# 407-485.net
KiCad netlist of a schematic drawn in Altium Designer
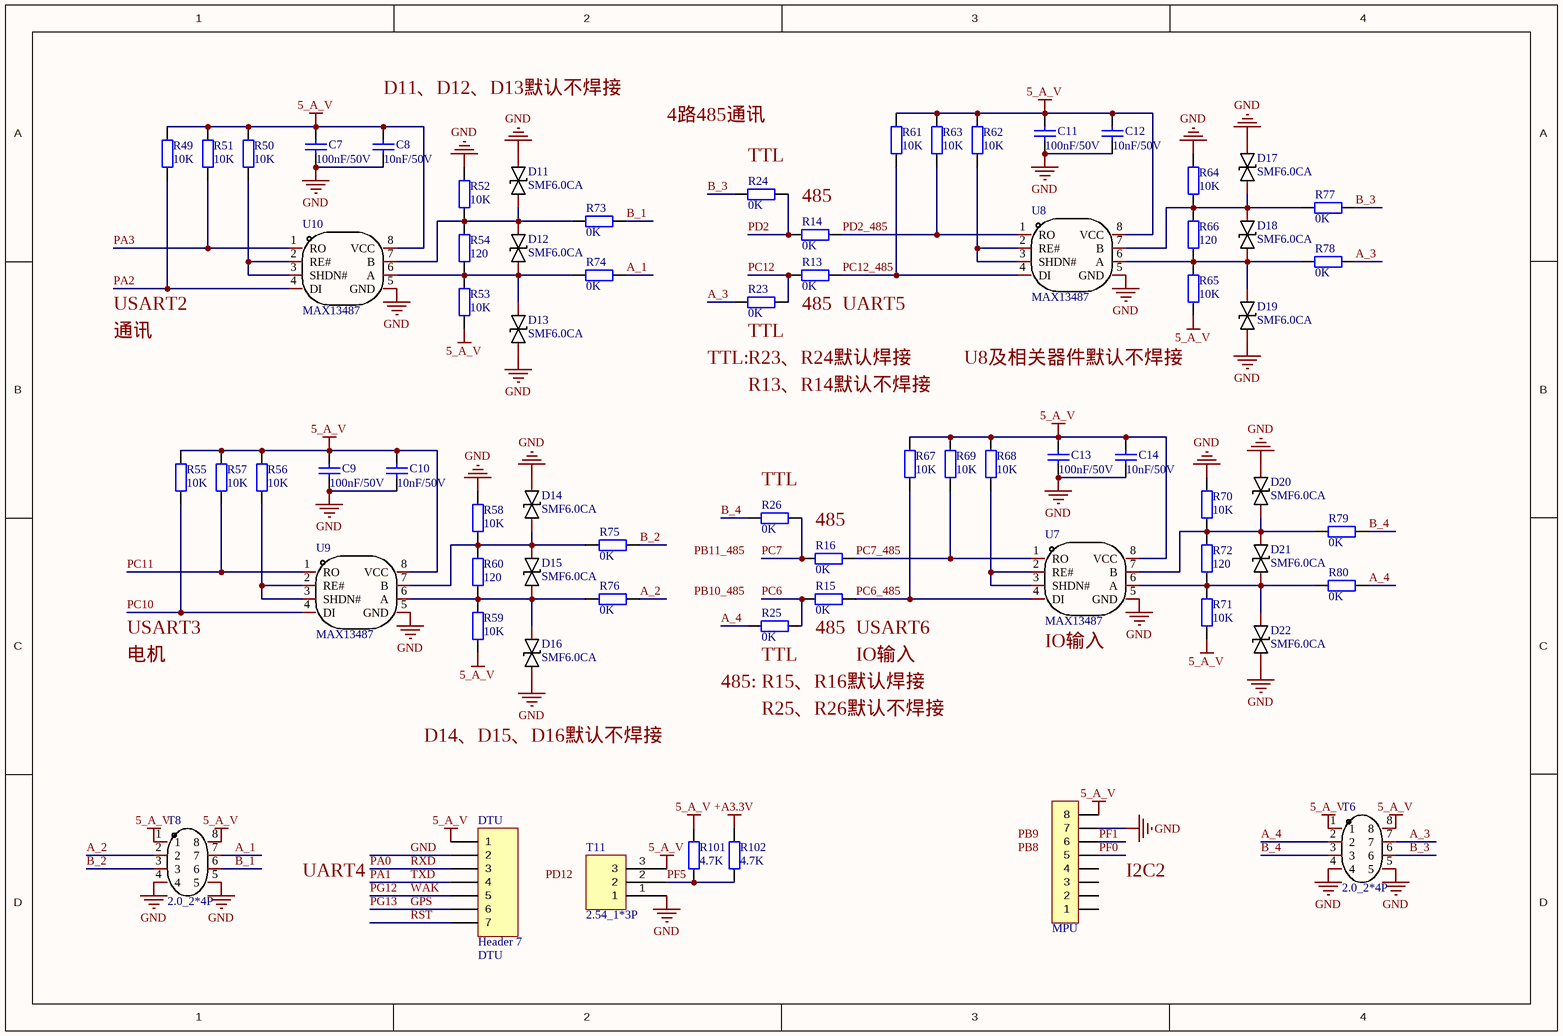
[diagram p0: 407-485.schdoc]

(export (version "E")
  (design (tool "Eeschema 10.0.6"))
  (components
    (comp (ref "C7")
      (value "100nF/50V")
      (description "Capacitor")
      (fields (field (name "PUBLISHER") "Altium Limited"))
      (libsource (lib "Miscellaneous Devices") (part "Cap"))
    )
    (comp (ref "C8")
      (value "10nF/50V")
      (description "Capacitor")
      (fields (field (name "PUBLISHER") "Altium Limited"))
      (libsource (lib "Miscellaneous Devices") (part "Cap"))
    )
    (comp (ref "C9")
      (value "100nF/50V")
      (description "Capacitor")
      (fields (field (name "PUBLISHER") "Altium Limited"))
      (libsource (lib "Miscellaneous Devices") (part "Cap"))
    )
    (comp (ref "C10")
      (value "10nF/50V")
      (description "Capacitor")
      (fields (field (name "PUBLISHER") "Altium Limited"))
      (libsource (lib "Miscellaneous Devices") (part "Cap"))
    )
    (comp (ref "C11")
      (value "100nF/50V")
      (description "Capacitor")
      (fields (field (name "PUBLISHER") "Altium Limited"))
      (libsource (lib "Miscellaneous Devices") (part "Cap"))
    )
    (comp (ref "C12")
      (value "10nF/50V")
      (description "Capacitor")
      (fields (field (name "PUBLISHER") "Altium Limited"))
      (libsource (lib "Miscellaneous Devices") (part "Cap"))
    )
    (comp (ref "C13")
      (value "100nF/50V")
      (description "Capacitor")
      (fields (field (name "PUBLISHER") "Altium Limited"))
      (libsource (lib "Miscellaneous Devices") (part "Cap"))
    )
    (comp (ref "C14")
      (value "10nF/50V")
      (description "Capacitor")
      (fields (field (name "PUBLISHER") "Altium Limited"))
      (libsource (lib "Miscellaneous Devices") (part "Cap"))
    )
    (comp (ref "D11")
      (value "SMF6.0CA")
      (footprint "SMF6.0CA")
      (libsource (lib "tianjin_2023") (part "SMF6.0CA"))
    )
    (comp (ref "D12")
      (value "SMF6.0CA")
      (footprint "SMF6.0CA")
      (libsource (lib "tianjin_2023") (part "SMF6.0CA"))
    )
    (comp (ref "D13")
      (value "SMF6.0CA")
      (footprint "SMF6.0CA")
      (libsource (lib "tianjin_2023") (part "SMF6.0CA"))
    )
    (comp (ref "D14")
      (value "SMF6.0CA")
      (footprint "SMF6.0CA")
      (libsource (lib "tianjin_2023") (part "SMF6.0CA"))
    )
    (comp (ref "D15")
      (value "SMF6.0CA")
      (footprint "SMF6.0CA")
      (libsource (lib "tianjin_2023") (part "SMF6.0CA"))
    )
    (comp (ref "D16")
      (value "SMF6.0CA")
      (footprint "SMF6.0CA")
      (libsource (lib "tianjin_2023") (part "SMF6.0CA"))
    )
    (comp (ref "D17")
      (value "SMF6.0CA")
      (footprint "SMF6.0CA")
      (libsource (lib "tianjin_2023") (part "SMF6.0CA"))
    )
    (comp (ref "D18")
      (value "SMF6.0CA")
      (footprint "SMF6.0CA")
      (libsource (lib "tianjin_2023") (part "SMF6.0CA"))
    )
    (comp (ref "D19")
      (value "SMF6.0CA")
      (footprint "SMF6.0CA")
      (libsource (lib "tianjin_2023") (part "SMF6.0CA"))
    )
    (comp (ref "D20")
      (value "SMF6.0CA")
      (footprint "SMF6.0CA")
      (libsource (lib "tianjin_2023") (part "SMF6.0CA"))
    )
    (comp (ref "D21")
      (value "SMF6.0CA")
      (footprint "SMF6.0CA")
      (libsource (lib "tianjin_2023") (part "SMF6.0CA"))
    )
    (comp (ref "D22")
      (value "SMF6.0CA")
      (footprint "SMF6.0CA")
      (libsource (lib "tianjin_2023") (part "SMF6.0CA"))
    )
    (comp (ref "DTU")
      (value "Header 7")
      (footprint "HDR1X7")
      (description "Header, 7-Pin")
      (fields (field (name "PUBLISHER") "Altium Limited"))
      (libsource (lib "Miscellaneous Connectors") (part "Header 7"))
    )
    (comp (ref "MPU")
      (value "HDR-1X8")
      (footprint "HDR2.54-M-LI-8P")
      (description "8P接插件")
      (fields (field (name "版权归属") "封装库来自淘宝 ID：黄晶宝石"))
      (libsource (lib "5.4 - 接插件-脚距2.54 (100mil) ") (part "Header 8"))
    )
    (comp (ref "R13")
      (value "0K")
      (footprint "R0603_L")
      (description "Resistor")
      (fields (field (name "PUBLISHER") "Altium Limited"))
      (libsource (lib "") (part "Res2_1"))
    )
    (comp (ref "R14")
      (value "0K")
      (footprint "R0603_L")
      (description "Resistor")
      (fields (field (name "PUBLISHER") "Altium Limited"))
      (libsource (lib "") (part "Res2_1"))
    )
    (comp (ref "R15")
      (value "0K")
      (footprint "R0603_L")
      (description "Resistor")
      (fields (field (name "PUBLISHER") "Altium Limited"))
      (libsource (lib "") (part "Res2_1"))
    )
    (comp (ref "R16")
      (value "0K")
      (footprint "R0603_L")
      (description "Resistor")
      (fields (field (name "PUBLISHER") "Altium Limited"))
      (libsource (lib "") (part "Res2_1"))
    )
    (comp (ref "R23")
      (value "0K")
      (footprint "R0603_L")
      (description "Resistor")
      (fields (field (name "PUBLISHER") "Altium Limited"))
      (libsource (lib "") (part "Res2_1"))
    )
    (comp (ref "R24")
      (value "0K")
      (footprint "R0603_L")
      (description "Resistor")
      (fields (field (name "PUBLISHER") "Altium Limited"))
      (libsource (lib "") (part "Res2_1"))
    )
    (comp (ref "R25")
      (value "0K")
      (footprint "R0603_L")
      (description "Resistor")
      (fields (field (name "PUBLISHER") "Altium Limited"))
      (libsource (lib "") (part "Res2_1"))
    )
    (comp (ref "R26")
      (value "0K")
      (footprint "R0603_L")
      (description "Resistor")
      (fields (field (name "PUBLISHER") "Altium Limited"))
      (libsource (lib "") (part "Res2_2"))
    )
    (comp (ref "R49")
      (value "10K")
      (footprint "R0603_L")
      (description "Resistor")
      (fields (field (name "PUBLISHER") "Altium Limited"))
      (libsource (lib "MOS motor driving module ") (part "Res2"))
    )
    (comp (ref "R50")
      (value "10K")
      (footprint "R0603_L")
      (description "Resistor")
      (fields (field (name "PUBLISHER") "Altium Limited"))
      (libsource (lib "MOS motor driving module ") (part "Res2"))
    )
    (comp (ref "R51")
      (value "10K")
      (footprint "R0603_L")
      (description "Resistor")
      (fields (field (name "PUBLISHER") "Altium Limited"))
      (libsource (lib "MOS motor driving module ") (part "Res2"))
    )
    (comp (ref "R52")
      (value "10K")
      (footprint "R0603_L")
      (description "Resistor")
      (fields (field (name "PUBLISHER") "Altium Limited"))
      (libsource (lib "MOS motor driving module ") (part "Res2"))
    )
    (comp (ref "R53")
      (value "10K")
      (footprint "R0603_L")
      (description "Resistor")
      (fields (field (name "PUBLISHER") "Altium Limited"))
      (libsource (lib "MOS motor driving module ") (part "Res2"))
    )
    (comp (ref "R54")
      (value "120")
      (footprint "R0603_L")
      (description "Resistor")
      (fields (field (name "PUBLISHER") "Altium Limited"))
      (libsource (lib "MOS motor driving module ") (part "Res2"))
    )
    (comp (ref "R55")
      (value "10K")
      (footprint "R0603_L")
      (description "Resistor")
      (fields (field (name "PUBLISHER") "Altium Limited"))
      (libsource (lib "MOS motor driving module ") (part "Res2"))
    )
    (comp (ref "R56")
      (value "10K")
      (footprint "R0603_L")
      (description "Resistor")
      (fields (field (name "PUBLISHER") "Altium Limited"))
      (libsource (lib "MOS motor driving module ") (part "Res2"))
    )
    (comp (ref "R57")
      (value "10K")
      (footprint "R0603_L")
      (description "Resistor")
      (fields (field (name "PUBLISHER") "Altium Limited"))
      (libsource (lib "MOS motor driving module ") (part "Res2"))
    )
    (comp (ref "R58")
      (value "10K")
      (footprint "R0603_L")
      (description "Resistor")
      (fields (field (name "PUBLISHER") "Altium Limited"))
      (libsource (lib "MOS motor driving module ") (part "Res2"))
    )
    (comp (ref "R59")
      (value "10K")
      (footprint "R0603_L")
      (description "Resistor")
      (fields (field (name "PUBLISHER") "Altium Limited"))
      (libsource (lib "MOS motor driving module ") (part "Res2"))
    )
    (comp (ref "R60")
      (value "120")
      (footprint "R0603_L")
      (description "Resistor")
      (fields (field (name "PUBLISHER") "Altium Limited"))
      (libsource (lib "MOS motor driving module ") (part "Res2"))
    )
    (comp (ref "R61")
      (value "10K")
      (footprint "R0603_L")
      (description "Resistor")
      (fields (field (name "PUBLISHER") "Altium Limited"))
      (libsource (lib "MOS motor driving module ") (part "Res2"))
    )
    (comp (ref "R62")
      (value "10K")
      (footprint "R0603_L")
      (description "Resistor")
      (fields (field (name "PUBLISHER") "Altium Limited"))
      (libsource (lib "MOS motor driving module ") (part "Res2"))
    )
    (comp (ref "R63")
      (value "10K")
      (footprint "R0603_L")
      (description "Resistor")
      (fields (field (name "PUBLISHER") "Altium Limited"))
      (libsource (lib "MOS motor driving module ") (part "Res2"))
    )
    (comp (ref "R64")
      (value "10K")
      (footprint "R0603_L")
      (description "Resistor")
      (fields (field (name "PUBLISHER") "Altium Limited"))
      (libsource (lib "MOS motor driving module ") (part "Res2"))
    )
    (comp (ref "R65")
      (value "10K")
      (footprint "R0603_L")
      (description "Resistor")
      (fields (field (name "PUBLISHER") "Altium Limited"))
      (libsource (lib "MOS motor driving module ") (part "Res2"))
    )
    (comp (ref "R66")
      (value "120")
      (footprint "R0603_L")
      (description "Resistor")
      (fields (field (name "PUBLISHER") "Altium Limited"))
      (libsource (lib "MOS motor driving module ") (part "Res2"))
    )
    (comp (ref "R67")
      (value "10K")
      (footprint "R0603_L")
      (description "Resistor")
      (fields (field (name "PUBLISHER") "Altium Limited"))
      (libsource (lib "MOS motor driving module ") (part "Res2"))
    )
    (comp (ref "R68")
      (value "10K")
      (footprint "R0603_L")
      (description "Resistor")
      (fields (field (name "PUBLISHER") "Altium Limited"))
      (libsource (lib "MOS motor driving module ") (part "Res2"))
    )
    (comp (ref "R69")
      (value "10K")
      (footprint "R0603_L")
      (description "Resistor")
      (fields (field (name "PUBLISHER") "Altium Limited"))
      (libsource (lib "MOS motor driving module ") (part "Res2"))
    )
    (comp (ref "R70")
      (value "10K")
      (footprint "R0603_L")
      (description "Resistor")
      (fields (field (name "PUBLISHER") "Altium Limited"))
      (libsource (lib "MOS motor driving module ") (part "Res2"))
    )
    (comp (ref "R71")
      (value "10K")
      (footprint "R0603_L")
      (description "Resistor")
      (fields (field (name "PUBLISHER") "Altium Limited"))
      (libsource (lib "MOS motor driving module ") (part "Res2"))
    )
    (comp (ref "R72")
      (value "120")
      (footprint "R0603_L")
      (description "Resistor")
      (fields (field (name "PUBLISHER") "Altium Limited"))
      (libsource (lib "MOS motor driving module ") (part "Res2"))
    )
    (comp (ref "R73")
      (value "0K")
      (footprint "R0603_L")
      (description "Resistor")
      (fields (field (name "PUBLISHER") "Altium Limited"))
      (libsource (lib "") (part "Res2_1"))
    )
    (comp (ref "R74")
      (value "0K")
      (footprint "R0603_L")
      (description "Resistor")
      (fields (field (name "PUBLISHER") "Altium Limited"))
      (libsource (lib "") (part "Res2_1"))
    )
    (comp (ref "R75")
      (value "0K")
      (footprint "R0603_L")
      (description "Resistor")
      (fields (field (name "PUBLISHER") "Altium Limited"))
      (libsource (lib "") (part "Res2_1"))
    )
    (comp (ref "R76")
      (value "0K")
      (footprint "R0603_L")
      (description "Resistor")
      (fields (field (name "PUBLISHER") "Altium Limited"))
      (libsource (lib "") (part "Res2_1"))
    )
    (comp (ref "R77")
      (value "0K")
      (footprint "R0603_L")
      (description "Resistor")
      (fields (field (name "PUBLISHER") "Altium Limited"))
      (libsource (lib "") (part "Res2_1"))
    )
    (comp (ref "R78")
      (value "0K")
      (footprint "R0603_L")
      (description "Resistor")
      (fields (field (name "PUBLISHER") "Altium Limited"))
      (libsource (lib "") (part "Res2_1"))
    )
    (comp (ref "R79")
      (value "0K")
      (footprint "R0603_L")
      (description "Resistor")
      (fields (field (name "PUBLISHER") "Altium Limited"))
      (libsource (lib "") (part "Res2_1"))
    )
    (comp (ref "R80")
      (value "0K")
      (footprint "R0603_L")
      (description "Resistor")
      (fields (field (name "PUBLISHER") "Altium Limited"))
      (libsource (lib "") (part "Res2_1"))
    )
    (comp (ref "R101")
      (value "4.7K")
      (description "Resistor")
      (fields (field (name "PUBLISHER") "Altium Limited"))
      (libsource (lib "MOS motor driving module ") (part "Res2"))
    )
    (comp (ref "R102")
      (value "4.7K")
      (description "Resistor")
      (fields (field (name "PUBLISHER") "Altium Limited"))
      (libsource (lib "MOS motor driving module ") (part "Res2"))
    )
    (comp (ref "T6")
      (value "2.0_2*4P")
      (footprint "2.0_2*4P")
      (libsource (lib "tianjin_2023") (part "2.0_2*4P"))
    )
    (comp (ref "T8")
      (value "2.0_2*4P")
      (footprint "2.0_2*4P")
      (libsource (lib "tianjin_2023") (part "2.0_2*4P"))
    )
    (comp (ref "T11")
      (value "2.54_1*3P")
      (footprint "2.54_1*3P")
      (libsource (lib "tianjin_2023") (part "2.54_1*3P"))
    )
    (comp (ref "U7")
      (value "MAX13487")
      (footprint "MAX13487")
      (libsource (lib "tianjin_2023") (part "MAX13487"))
    )
    (comp (ref "U8")
      (value "MAX13487")
      (footprint "MAX13487")
      (libsource (lib "tianjin_2023") (part "MAX13487"))
    )
    (comp (ref "U9")
      (value "MAX13487")
      (footprint "MAX13487")
      (libsource (lib "tianjin_2023") (part "MAX13487"))
    )
    (comp (ref "U10")
      (value "MAX13487")
      (footprint "MAX13487")
      (libsource (lib "tianjin_2023") (part "MAX13487"))
    )
  )
  (nets
    (net (code "1") (name "+A3.3V") (class "Default")
      (node (ref "R102") (pin "2") (pinfunction "2_2") (pintype "passive"))
    )
    (net (code "2") (name "/A_1") (class "Default")
      (node (ref "R74") (pin "1") (pinfunction "1_1") (pintype "passive"))
      (node (ref "T8") (pin "7") (pinfunction "7_7") (pintype "passive"))
    )
    (net (code "3") (name "/A_2") (class "Default")
      (node (ref "R76") (pin "1") (pinfunction "1_1") (pintype "passive"))
      (node (ref "T8") (pin "2") (pinfunction "2_2") (pintype "passive"))
    )
    (net (code "4") (name "/A_3") (class "Default")
      (node (ref "R23") (pin "2") (pinfunction "2_2") (pintype "passive"))
      (node (ref "R78") (pin "1") (pinfunction "1_1") (pintype "passive"))
      (node (ref "T6") (pin "7") (pinfunction "7_7") (pintype "passive"))
    )
    (net (code "5") (name "/A_4") (class "Default")
      (node (ref "R25") (pin "2") (pinfunction "2_2") (pintype "passive"))
      (node (ref "R80") (pin "1") (pinfunction "1_1") (pintype "passive"))
      (node (ref "T6") (pin "2") (pinfunction "2_2") (pintype "passive"))
    )
    (net (code "6") (name "/B_1") (class "Default")
      (node (ref "R73") (pin "1") (pinfunction "1_1") (pintype "passive"))
      (node (ref "T8") (pin "6") (pinfunction "6_6") (pintype "passive"))
    )
    (net (code "7") (name "/B_2") (class "Default")
      (node (ref "R75") (pin "1") (pinfunction "1_1") (pintype "passive"))
      (node (ref "T8") (pin "3") (pinfunction "3_3") (pintype "passive"))
    )
    (net (code "8") (name "/B_3") (class "Default")
      (node (ref "R24") (pin "2") (pinfunction "2_2") (pintype "passive"))
      (node (ref "R77") (pin "1") (pinfunction "1_1") (pintype "passive"))
      (node (ref "T6") (pin "6") (pinfunction "6_6") (pintype "passive"))
    )
    (net (code "9") (name "/B_4") (class "Default")
      (node (ref "R26") (pin "1") (pinfunction "1_1") (pintype "passive"))
      (node (ref "R79") (pin "1") (pinfunction "1_1") (pintype "passive"))
      (node (ref "T6") (pin "3") (pinfunction "3_3") (pintype "passive"))
    )
    (net (code "10") (name "/GPS") (class "Default")
      (node (ref "DTU") (pin "6") (pinfunction "6_6") (pintype "passive"))
    )
    (net (code "11") (name "/PA0") (class "Default")
      (node (ref "DTU") (pin "3") (pinfunction "3_3") (pintype "passive"))
    )
    (net (code "12") (name "/PA1") (class "Default")
      (node (ref "DTU") (pin "4") (pinfunction "4_4") (pintype "passive"))
    )
    (net (code "13") (name "/PA2") (class "Default")
      (node (ref "R49") (pin "1") (pinfunction "1_1") (pintype "passive"))
      (node (ref "U10") (pin "4") (pinfunction "DI_4") (pintype "passive"))
    )
    (net (code "14") (name "/PA3") (class "Default")
      (node (ref "R51") (pin "1") (pinfunction "1_1") (pintype "passive"))
      (node (ref "U10") (pin "1") (pinfunction "RO_1") (pintype "passive"))
    )
    (net (code "19") (name "/PC6") (class "Default")
      (node (ref "R15") (pin "2") (pinfunction "2_2") (pintype "passive"))
      (node (ref "R25") (pin "1") (pinfunction "1_1") (pintype "passive"))
    )
    (net (code "20") (name "/PC6_485") (class "Default")
      (node (ref "R15") (pin "1") (pinfunction "1_1") (pintype "passive"))
      (node (ref "R67") (pin "1") (pinfunction "1_1") (pintype "passive"))
      (node (ref "U7") (pin "4") (pinfunction "DI_4") (pintype "passive"))
    )
    (net (code "21") (name "/PC7") (class "Default")
      (node (ref "R16") (pin "2") (pinfunction "2_2") (pintype "passive"))
      (node (ref "R26") (pin "2") (pinfunction "2_2") (pintype "passive"))
    )
    (net (code "22") (name "/PC7_485") (class "Default")
      (node (ref "R16") (pin "1") (pinfunction "1_1") (pintype "passive"))
      (node (ref "R69") (pin "1") (pinfunction "1_1") (pintype "passive"))
      (node (ref "U7") (pin "1") (pinfunction "RO_1") (pintype "passive"))
    )
    (net (code "23") (name "/PC10") (class "Default")
      (node (ref "R55") (pin "1") (pinfunction "1_1") (pintype "passive"))
      (node (ref "U9") (pin "4") (pinfunction "DI_4") (pintype "passive"))
    )
    (net (code "24") (name "/PC11") (class "Default")
      (node (ref "R57") (pin "1") (pinfunction "1_1") (pintype "passive"))
      (node (ref "U9") (pin "1") (pinfunction "RO_1") (pintype "passive"))
    )
    (net (code "25") (name "/PC12") (class "Default")
      (node (ref "R13") (pin "2") (pinfunction "2_2") (pintype "passive"))
      (node (ref "R23") (pin "1") (pinfunction "1_1") (pintype "passive"))
    )
    (net (code "26") (name "/PC12_485") (class "Default")
      (node (ref "R13") (pin "1") (pinfunction "1_1") (pintype "passive"))
      (node (ref "R61") (pin "1") (pinfunction "1_1") (pintype "passive"))
      (node (ref "U8") (pin "4") (pinfunction "DI_4") (pintype "passive"))
    )
    (net (code "27") (name "/PD2") (class "Default")
      (node (ref "R14") (pin "2") (pinfunction "2_2") (pintype "passive"))
      (node (ref "R24") (pin "1") (pinfunction "1_1") (pintype "passive"))
    )
    (net (code "28") (name "/PD2_485") (class "Default")
      (node (ref "R14") (pin "1") (pinfunction "1_1") (pintype "passive"))
      (node (ref "R63") (pin "1") (pinfunction "1_1") (pintype "passive"))
      (node (ref "U8") (pin "1") (pinfunction "RO_1") (pintype "passive"))
    )
    (net (code "30") (name "/PF0") (class "Default")
      (node (ref "MPU") (pin "5") (pinfunction "5_5") (pintype "passive"))
    )
    (net (code "31") (name "/PF1") (class "Default")
      (node (ref "MPU") (pin "6") (pinfunction "6_6") (pintype "passive"))
    )
    (net (code "32") (name "/PF5") (class "Default")
      (node (ref "R101") (pin "1") (pinfunction "1_1") (pintype "passive"))
      (node (ref "R102") (pin "1") (pinfunction "1_1") (pintype "passive"))
      (node (ref "T11") (pin "2") (pinfunction "2_2") (pintype "passive"))
    )
    (net (code "33") (name "/PG12") (class "Default")
      (node (ref "DTU") (pin "5") (pinfunction "5_5") (pintype "passive"))
    )
    (net (code "34") (name "/RST") (class "Default")
      (node (ref "DTU") (pin "7") (pinfunction "7_7") (pintype "passive"))
    )
    (net (code "35") (name "5_A_V") (class "Default")
      (node (ref "C10") (pin "1") (pinfunction "1_1") (pintype "passive"))
      (node (ref "C11") (pin "1") (pinfunction "1_1") (pintype "passive"))
      (node (ref "C12") (pin "1") (pinfunction "1_1") (pintype "passive"))
      (node (ref "C13") (pin "1") (pinfunction "1_1") (pintype "passive"))
      (node (ref "C14") (pin "1") (pinfunction "1_1") (pintype "passive"))
      (node (ref "C7") (pin "1") (pinfunction "1_1") (pintype "passive"))
      (node (ref "C8") (pin "1") (pinfunction "1_1") (pintype "passive"))
      (node (ref "C9") (pin "1") (pinfunction "1_1") (pintype "passive"))
      (node (ref "DTU") (pin "1") (pinfunction "1_1") (pintype "passive"))
      (node (ref "MPU") (pin "8") (pinfunction "8_8") (pintype "passive"))
      (node (ref "R101") (pin "2") (pinfunction "2_2") (pintype "passive"))
      (node (ref "R49") (pin "2") (pinfunction "2_2") (pintype "passive"))
      (node (ref "R50") (pin "2") (pinfunction "2_2") (pintype "passive"))
      (node (ref "R51") (pin "2") (pinfunction "2_2") (pintype "passive"))
      (node (ref "R53") (pin "1") (pinfunction "1_1") (pintype "passive"))
      (node (ref "R55") (pin "2") (pinfunction "2_2") (pintype "passive"))
      (node (ref "R56") (pin "2") (pinfunction "2_2") (pintype "passive"))
      (node (ref "R57") (pin "2") (pinfunction "2_2") (pintype "passive"))
      (node (ref "R59") (pin "1") (pinfunction "1_1") (pintype "passive"))
      (node (ref "R61") (pin "2") (pinfunction "2_2") (pintype "passive"))
      (node (ref "R62") (pin "2") (pinfunction "2_2") (pintype "passive"))
      (node (ref "R63") (pin "2") (pinfunction "2_2") (pintype "passive"))
      (node (ref "R65") (pin "1") (pinfunction "1_1") (pintype "passive"))
      (node (ref "R67") (pin "2") (pinfunction "2_2") (pintype "passive"))
      (node (ref "R68") (pin "2") (pinfunction "2_2") (pintype "passive"))
      (node (ref "R69") (pin "2") (pinfunction "2_2") (pintype "passive"))
      (node (ref "R71") (pin "1") (pinfunction "1_1") (pintype "passive"))
      (node (ref "T11") (pin "3") (pinfunction "3_3") (pintype "passive"))
      (node (ref "T6") (pin "1") (pinfunction "1_1") (pintype "passive"))
      (node (ref "T6") (pin "8") (pinfunction "8_8") (pintype "passive"))
      (node (ref "T8") (pin "1") (pinfunction "1_1") (pintype "passive"))
      (node (ref "T8") (pin "8") (pinfunction "8_8") (pintype "passive"))
      (node (ref "U10") (pin "8") (pinfunction "VCC_8") (pintype "passive"))
      (node (ref "U7") (pin "8") (pinfunction "VCC_8") (pintype "passive"))
      (node (ref "U8") (pin "8") (pinfunction "VCC_8") (pintype "passive"))
      (node (ref "U9") (pin "8") (pinfunction "VCC_8") (pintype "passive"))
    )
    (net (code "36") (name "GND") (class "Default")
      (node (ref "C10") (pin "2") (pinfunction "2_2") (pintype "passive"))
      (node (ref "C11") (pin "2") (pinfunction "2_2") (pintype "passive"))
      (node (ref "C12") (pin "2") (pinfunction "2_2") (pintype "passive"))
      (node (ref "C13") (pin "2") (pinfunction "2_2") (pintype "passive"))
      (node (ref "C14") (pin "2") (pinfunction "2_2") (pintype "passive"))
      (node (ref "C7") (pin "2") (pinfunction "2_2") (pintype "passive"))
      (node (ref "C8") (pin "2") (pinfunction "2_2") (pintype "passive"))
      (node (ref "C9") (pin "2") (pinfunction "2_2") (pintype "passive"))
      (node (ref "D11") (pin "2") (pinfunction "2_2") (pintype "passive"))
      (node (ref "D13") (pin "1") (pinfunction "1_1") (pintype "passive"))
      (node (ref "D14") (pin "2") (pinfunction "2_2") (pintype "passive"))
      (node (ref "D16") (pin "1") (pinfunction "1_1") (pintype "passive"))
      (node (ref "D17") (pin "2") (pinfunction "2_2") (pintype "passive"))
      (node (ref "D19") (pin "1") (pinfunction "1_1") (pintype "passive"))
      (node (ref "D20") (pin "2") (pinfunction "2_2") (pintype "passive"))
      (node (ref "D22") (pin "1") (pinfunction "1_1") (pintype "passive"))
      (node (ref "DTU") (pin "2") (pinfunction "2_2") (pintype "passive"))
      (node (ref "MPU") (pin "7") (pinfunction "7_7") (pintype "passive"))
      (node (ref "R52") (pin "2") (pinfunction "2_2") (pintype "passive"))
      (node (ref "R58") (pin "2") (pinfunction "2_2") (pintype "passive"))
      (node (ref "R64") (pin "2") (pinfunction "2_2") (pintype "passive"))
      (node (ref "R70") (pin "2") (pinfunction "2_2") (pintype "passive"))
      (node (ref "T11") (pin "1") (pinfunction "1_1") (pintype "passive"))
      (node (ref "T6") (pin "4") (pinfunction "4_4") (pintype "passive"))
      (node (ref "T6") (pin "5") (pinfunction "5_5") (pintype "passive"))
      (node (ref "T8") (pin "4") (pinfunction "4_4") (pintype "passive"))
      (node (ref "T8") (pin "5") (pinfunction "5_5") (pintype "passive"))
      (node (ref "U10") (pin "5") (pinfunction "GND_5") (pintype "passive"))
      (node (ref "U7") (pin "5") (pinfunction "GND_5") (pintype "passive"))
      (node (ref "U8") (pin "5") (pinfunction "GND_5") (pintype "passive"))
      (node (ref "U9") (pin "5") (pinfunction "GND_5") (pintype "passive"))
    )
    (net (code "37") (name "Net-(U7-A)") (class "Default")
      (node (ref "D21") (pin "1") (pinfunction "1_1") (pintype "passive"))
      (node (ref "D22") (pin "2") (pinfunction "2_2") (pintype "passive"))
      (node (ref "R71") (pin "2") (pinfunction "2_2") (pintype "passive"))
      (node (ref "R72") (pin "1") (pinfunction "1_1") (pintype "passive"))
      (node (ref "R80") (pin "2") (pinfunction "2_2") (pintype "passive"))
      (node (ref "U7") (pin "6") (pinfunction "A_6") (pintype "passive"))
    )
    (net (code "38") (name "Net-(U7-B)") (class "Default")
      (node (ref "D20") (pin "1") (pinfunction "1_1") (pintype "passive"))
      (node (ref "D21") (pin "2") (pinfunction "2_2") (pintype "passive"))
      (node (ref "R70") (pin "1") (pinfunction "1_1") (pintype "passive"))
      (node (ref "R72") (pin "2") (pinfunction "2_2") (pintype "passive"))
      (node (ref "R79") (pin "2") (pinfunction "2_2") (pintype "passive"))
      (node (ref "U7") (pin "7") (pinfunction "B_7") (pintype "passive"))
    )
    (net (code "39") (name "Net-(U7-RE#)") (class "Default")
      (node (ref "R68") (pin "1") (pinfunction "1_1") (pintype "passive"))
      (node (ref "U7") (pin "2") (pinfunction "RE#_2") (pintype "passive"))
      (node (ref "U7") (pin "3") (pinfunction "SHDN#_3") (pintype "passive"))
    )
    (net (code "40") (name "Net-(U8-A)") (class "Default")
      (node (ref "D18") (pin "1") (pinfunction "1_1") (pintype "passive"))
      (node (ref "D19") (pin "2") (pinfunction "2_2") (pintype "passive"))
      (node (ref "R65") (pin "2") (pinfunction "2_2") (pintype "passive"))
      (node (ref "R66") (pin "1") (pinfunction "1_1") (pintype "passive"))
      (node (ref "R78") (pin "2") (pinfunction "2_2") (pintype "passive"))
      (node (ref "U8") (pin "6") (pinfunction "A_6") (pintype "passive"))
    )
    (net (code "41") (name "Net-(U8-B)") (class "Default")
      (node (ref "D17") (pin "1") (pinfunction "1_1") (pintype "passive"))
      (node (ref "D18") (pin "2") (pinfunction "2_2") (pintype "passive"))
      (node (ref "R64") (pin "1") (pinfunction "1_1") (pintype "passive"))
      (node (ref "R66") (pin "2") (pinfunction "2_2") (pintype "passive"))
      (node (ref "R77") (pin "2") (pinfunction "2_2") (pintype "passive"))
      (node (ref "U8") (pin "7") (pinfunction "B_7") (pintype "passive"))
    )
    (net (code "42") (name "Net-(U8-RE#)") (class "Default")
      (node (ref "R62") (pin "1") (pinfunction "1_1") (pintype "passive"))
      (node (ref "U8") (pin "2") (pinfunction "RE#_2") (pintype "passive"))
      (node (ref "U8") (pin "3") (pinfunction "SHDN#_3") (pintype "passive"))
    )
    (net (code "43") (name "Net-(U9-A)") (class "Default")
      (node (ref "D15") (pin "1") (pinfunction "1_1") (pintype "passive"))
      (node (ref "D16") (pin "2") (pinfunction "2_2") (pintype "passive"))
      (node (ref "R59") (pin "2") (pinfunction "2_2") (pintype "passive"))
      (node (ref "R60") (pin "1") (pinfunction "1_1") (pintype "passive"))
      (node (ref "R76") (pin "2") (pinfunction "2_2") (pintype "passive"))
      (node (ref "U9") (pin "6") (pinfunction "A_6") (pintype "passive"))
    )
    (net (code "44") (name "Net-(U9-B)") (class "Default")
      (node (ref "D14") (pin "1") (pinfunction "1_1") (pintype "passive"))
      (node (ref "D15") (pin "2") (pinfunction "2_2") (pintype "passive"))
      (node (ref "R58") (pin "1") (pinfunction "1_1") (pintype "passive"))
      (node (ref "R60") (pin "2") (pinfunction "2_2") (pintype "passive"))
      (node (ref "R75") (pin "2") (pinfunction "2_2") (pintype "passive"))
      (node (ref "U9") (pin "7") (pinfunction "B_7") (pintype "passive"))
    )
    (net (code "45") (name "Net-(U9-RE#)") (class "Default")
      (node (ref "R56") (pin "1") (pinfunction "1_1") (pintype "passive"))
      (node (ref "U9") (pin "2") (pinfunction "RE#_2") (pintype "passive"))
      (node (ref "U9") (pin "3") (pinfunction "SHDN#_3") (pintype "passive"))
    )
    (net (code "46") (name "Net-(U10-A)") (class "Default")
      (node (ref "D12") (pin "1") (pinfunction "1_1") (pintype "passive"))
      (node (ref "D13") (pin "2") (pinfunction "2_2") (pintype "passive"))
      (node (ref "R53") (pin "2") (pinfunction "2_2") (pintype "passive"))
      (node (ref "R54") (pin "1") (pinfunction "1_1") (pintype "passive"))
      (node (ref "R74") (pin "2") (pinfunction "2_2") (pintype "passive"))
      (node (ref "U10") (pin "6") (pinfunction "A_6") (pintype "passive"))
    )
    (net (code "47") (name "Net-(U10-B)") (class "Default")
      (node (ref "D11") (pin "1") (pinfunction "1_1") (pintype "passive"))
      (node (ref "D12") (pin "2") (pinfunction "2_2") (pintype "passive"))
      (node (ref "R52") (pin "1") (pinfunction "1_1") (pintype "passive"))
      (node (ref "R54") (pin "2") (pinfunction "2_2") (pintype "passive"))
      (node (ref "R73") (pin "2") (pinfunction "2_2") (pintype "passive"))
      (node (ref "U10") (pin "7") (pinfunction "B_7") (pintype "passive"))
    )
    (net (code "48") (name "Net-(U10-RE#)") (class "Default")
      (node (ref "R50") (pin "1") (pinfunction "1_1") (pintype "passive"))
      (node (ref "U10") (pin "2") (pinfunction "RE#_2") (pintype "passive"))
      (node (ref "U10") (pin "3") (pinfunction "SHDN#_3") (pintype "passive"))
    )
    (net (code "49") (name "unconnected-(MPU-Pad1)") (class "Default")
      (node (ref "MPU") (pin "1") (pinfunction "1_1") (pintype "passive"))
    )
    (net (code "50") (name "unconnected-(MPU-Pad2)") (class "Default")
      (node (ref "MPU") (pin "2") (pinfunction "2_2") (pintype "passive"))
    )
    (net (code "51") (name "unconnected-(MPU-Pad3)") (class "Default")
      (node (ref "MPU") (pin "3") (pinfunction "3_3") (pintype "passive"))
    )
    (net (code "52") (name "unconnected-(MPU-Pad4)") (class "Default")
      (node (ref "MPU") (pin "4") (pinfunction "4_4") (pintype "passive"))
    )
  )
)
